# 07_-_TEMP_PROXIMITY_SENSORS.net
KiCad netlist of a schematic drawn in Altium Designer
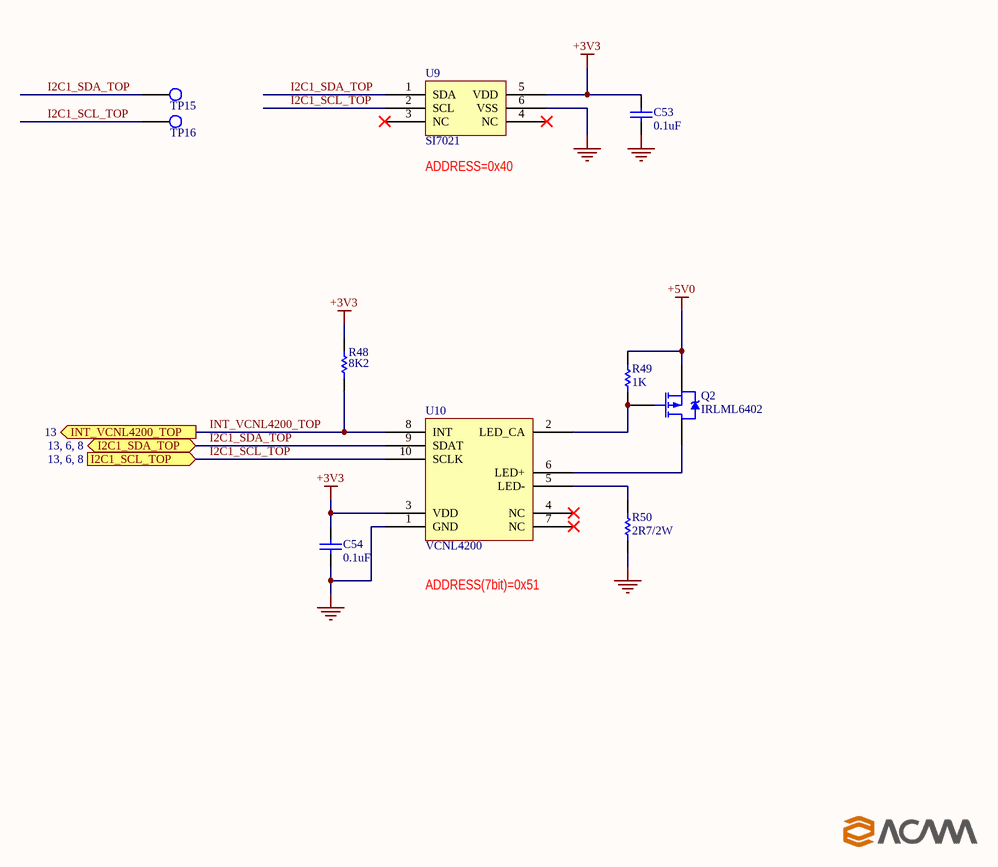
[diagram p0: [07] - TEMP, PROXIMITY SENSORS.SchDoc]

(export (version "E")
  (design (tool "Eeschema 10.0.6"))
  (components
    (comp (ref "C53")
      (value "0.1uF")
      (footprint "0805_C_AUTO")
      (description "Non-Pol SMD Capacitor")
      (libsource (lib "Farzan Custom Library") (part "Cap SMD"))
    )
    (comp (ref "C54")
      (value "0.1uF")
      (footprint "0805_C_AUTO")
      (description "Non-Pol SMD Capacitor")
      (libsource (lib "Farzan Custom Library") (part "Cap SMD"))
    )
    (comp (ref "Q2")
      (value "IRLML6402")
      (footprint "SOT23")
      (description "P-Channel Mosfet")
      (fields (field (name "MANUFACTURER PART NUM") "IRLML6402TRPBF"))
      (libsource (lib "Farzan Custom Library") (part "MOSFET P-CH"))
    )
    (comp (ref "R48")
      (value "8K2")
      (footprint "0805_R_AUTO")
      (description "SMD Resistor")
      (fields (field (name "TOLERANCE") "5%"))
      (libsource (lib "Farzan Custom Library") (part "Res SMD"))
    )
    (comp (ref "R49")
      (value "1K")
      (footprint "0805_R_AUTO")
      (description "SMD Resistor")
      (fields (field (name "TOLERANCE") "5%"))
      (libsource (lib "Farzan Custom Library") (part "Res SMD"))
    )
    (comp (ref "R50")
      (value "2R7/2W")
      (footprint "2512_R")
      (description "SMD Resistor")
      (fields (field (name "TOLERANCE") "5%") (field (name "MANUFACTURER PART NUM") "AC2512JK-7W2R7L"))
      (libsource (lib "Farzan Custom Library") (part "Res SMD"))
    )
    (comp (ref "TP15")
      (value "Test Point")
      (footprint "PIN_1mm")
      (description "Test Point Footprint")
      (libsource (lib "Farzan Custom Library") (part "Test Point"))
    )
    (comp (ref "TP16")
      (value "Test Point")
      (footprint "PIN_1mm")
      (description "Test Point Footprint")
      (libsource (lib "Farzan Custom Library") (part "Test Point"))
    )
    (comp (ref "U9")
      (value "SI7021")
      (footprint "DFN-6")
      (description "I2C HUMIDITY AND TEMPERATURE SENSOR")
      (libsource (lib "Farzan Custom Library") (part "SI7021"))
    )
    (comp (ref "U10")
      (value "VCNL4200")
      (footprint "VCNL4200")
      (description "High Sensitivity Long Distance Proximity and Ambient Light Sensor With I2C Interface")
      (libsource (lib "Farzan Custom Library") (part "VCNL4200"))
    )
  )
  (nets
    (net (code "1") (name "+3V3") (class "Default")
      (node (ref "C53") (pin "2") (pinfunction "2_2") (pintype "passive"))
      (node (ref "C54") (pin "2") (pinfunction "2_2") (pintype "passive"))
      (node (ref "R48") (pin "1") (pinfunction "1_1") (pintype "passive"))
      (node (ref "U10") (pin "3") (pinfunction "VDD_3") (pintype "power_in"))
      (node (ref "U9") (pin "5") (pinfunction "VDD_5") (pintype "power_in"))
    )
    (net (code "2") (name "+5V0") (class "Default")
      (node (ref "Q2") (pin "2") (pinfunction "S_2") (pintype "passive"))
      (node (ref "R49") (pin "2") (pinfunction "2_2") (pintype "passive"))
    )
    (net (code "3") (name "/I2C1_SCL_TOP") (class "Default")
      (node (ref "TP16") (pin "1") (pinfunction "1_1") (pintype "passive"))
      (node (ref "U10") (pin "10") (pinfunction "SCLK_10") (pintype "passive"))
      (node (ref "U9") (pin "2") (pinfunction "SCL_2") (pintype "passive"))
    )
    (net (code "4") (name "/I2C1_SDA_TOP") (class "Default")
      (node (ref "TP15") (pin "1") (pinfunction "1_1") (pintype "passive"))
      (node (ref "U10") (pin "9") (pinfunction "SDAT_9") (pintype "passive"))
      (node (ref "U9") (pin "1") (pinfunction "SDA_1") (pintype "passive"))
    )
    (net (code "5") (name "/INT_VCNL4200_TOP") (class "Default")
      (node (ref "R48") (pin "2") (pinfunction "2_2") (pintype "passive"))
      (node (ref "U10") (pin "8") (pinfunction "INT_8") (pintype "passive"))
    )
    (net (code "6") (name "GND") (class "Default")
      (node (ref "C53") (pin "1") (pinfunction "1_1") (pintype "passive"))
      (node (ref "C54") (pin "1") (pinfunction "1_1") (pintype "passive"))
      (node (ref "R50") (pin "1") (pinfunction "1_1") (pintype "passive"))
      (node (ref "U10") (pin "1") (pinfunction "GND_1") (pintype "power_in"))
      (node (ref "U9") (pin "6") (pinfunction "VSS_6") (pintype "power_in"))
    )
    (net (code "7") (name "Net-(Q2-D)") (class "Default")
      (node (ref "Q2") (pin "3") (pinfunction "D_3") (pintype "passive"))
      (node (ref "U10") (pin "6") (pinfunction "LED+_6") (pintype "passive"))
    )
    (net (code "8") (name "Net-(Q2-G)") (class "Default")
      (node (ref "Q2") (pin "1") (pinfunction "G_1") (pintype "passive"))
      (node (ref "R49") (pin "1") (pinfunction "1_1") (pintype "passive"))
      (node (ref "U10") (pin "2") (pinfunction "LED_CA_2") (pintype "passive"))
    )
    (net (code "9") (name "Net-(U10-LED-)") (class "Default")
      (node (ref "R50") (pin "2") (pinfunction "2_2") (pintype "passive"))
      (node (ref "U10") (pin "5") (pinfunction "LED-_5") (pintype "passive"))
    )
    (net (code "10") (name "unconnected-(U9-NC-Pad3)") (class "Default")
      (node (ref "U9") (pin "3") (pinfunction "NC_3") (pintype "passive+no_connect"))
    )
    (net (code "11") (name "unconnected-(U9-NC-Pad4)") (class "Default")
      (node (ref "U9") (pin "4") (pinfunction "NC_4") (pintype "passive+no_connect"))
    )
    (net (code "12") (name "unconnected-(U10-NC-Pad4)") (class "Default")
      (node (ref "U10") (pin "4") (pinfunction "NC_4") (pintype "passive+no_connect"))
    )
    (net (code "13") (name "unconnected-(U10-NC-Pad7)") (class "Default")
      (node (ref "U10") (pin "7") (pinfunction "NC_7") (pintype "passive+no_connect"))
    )
  )
)
